# SUBBOARD-MCU.net
KiCad netlist of a schematic drawn in Altium Designer
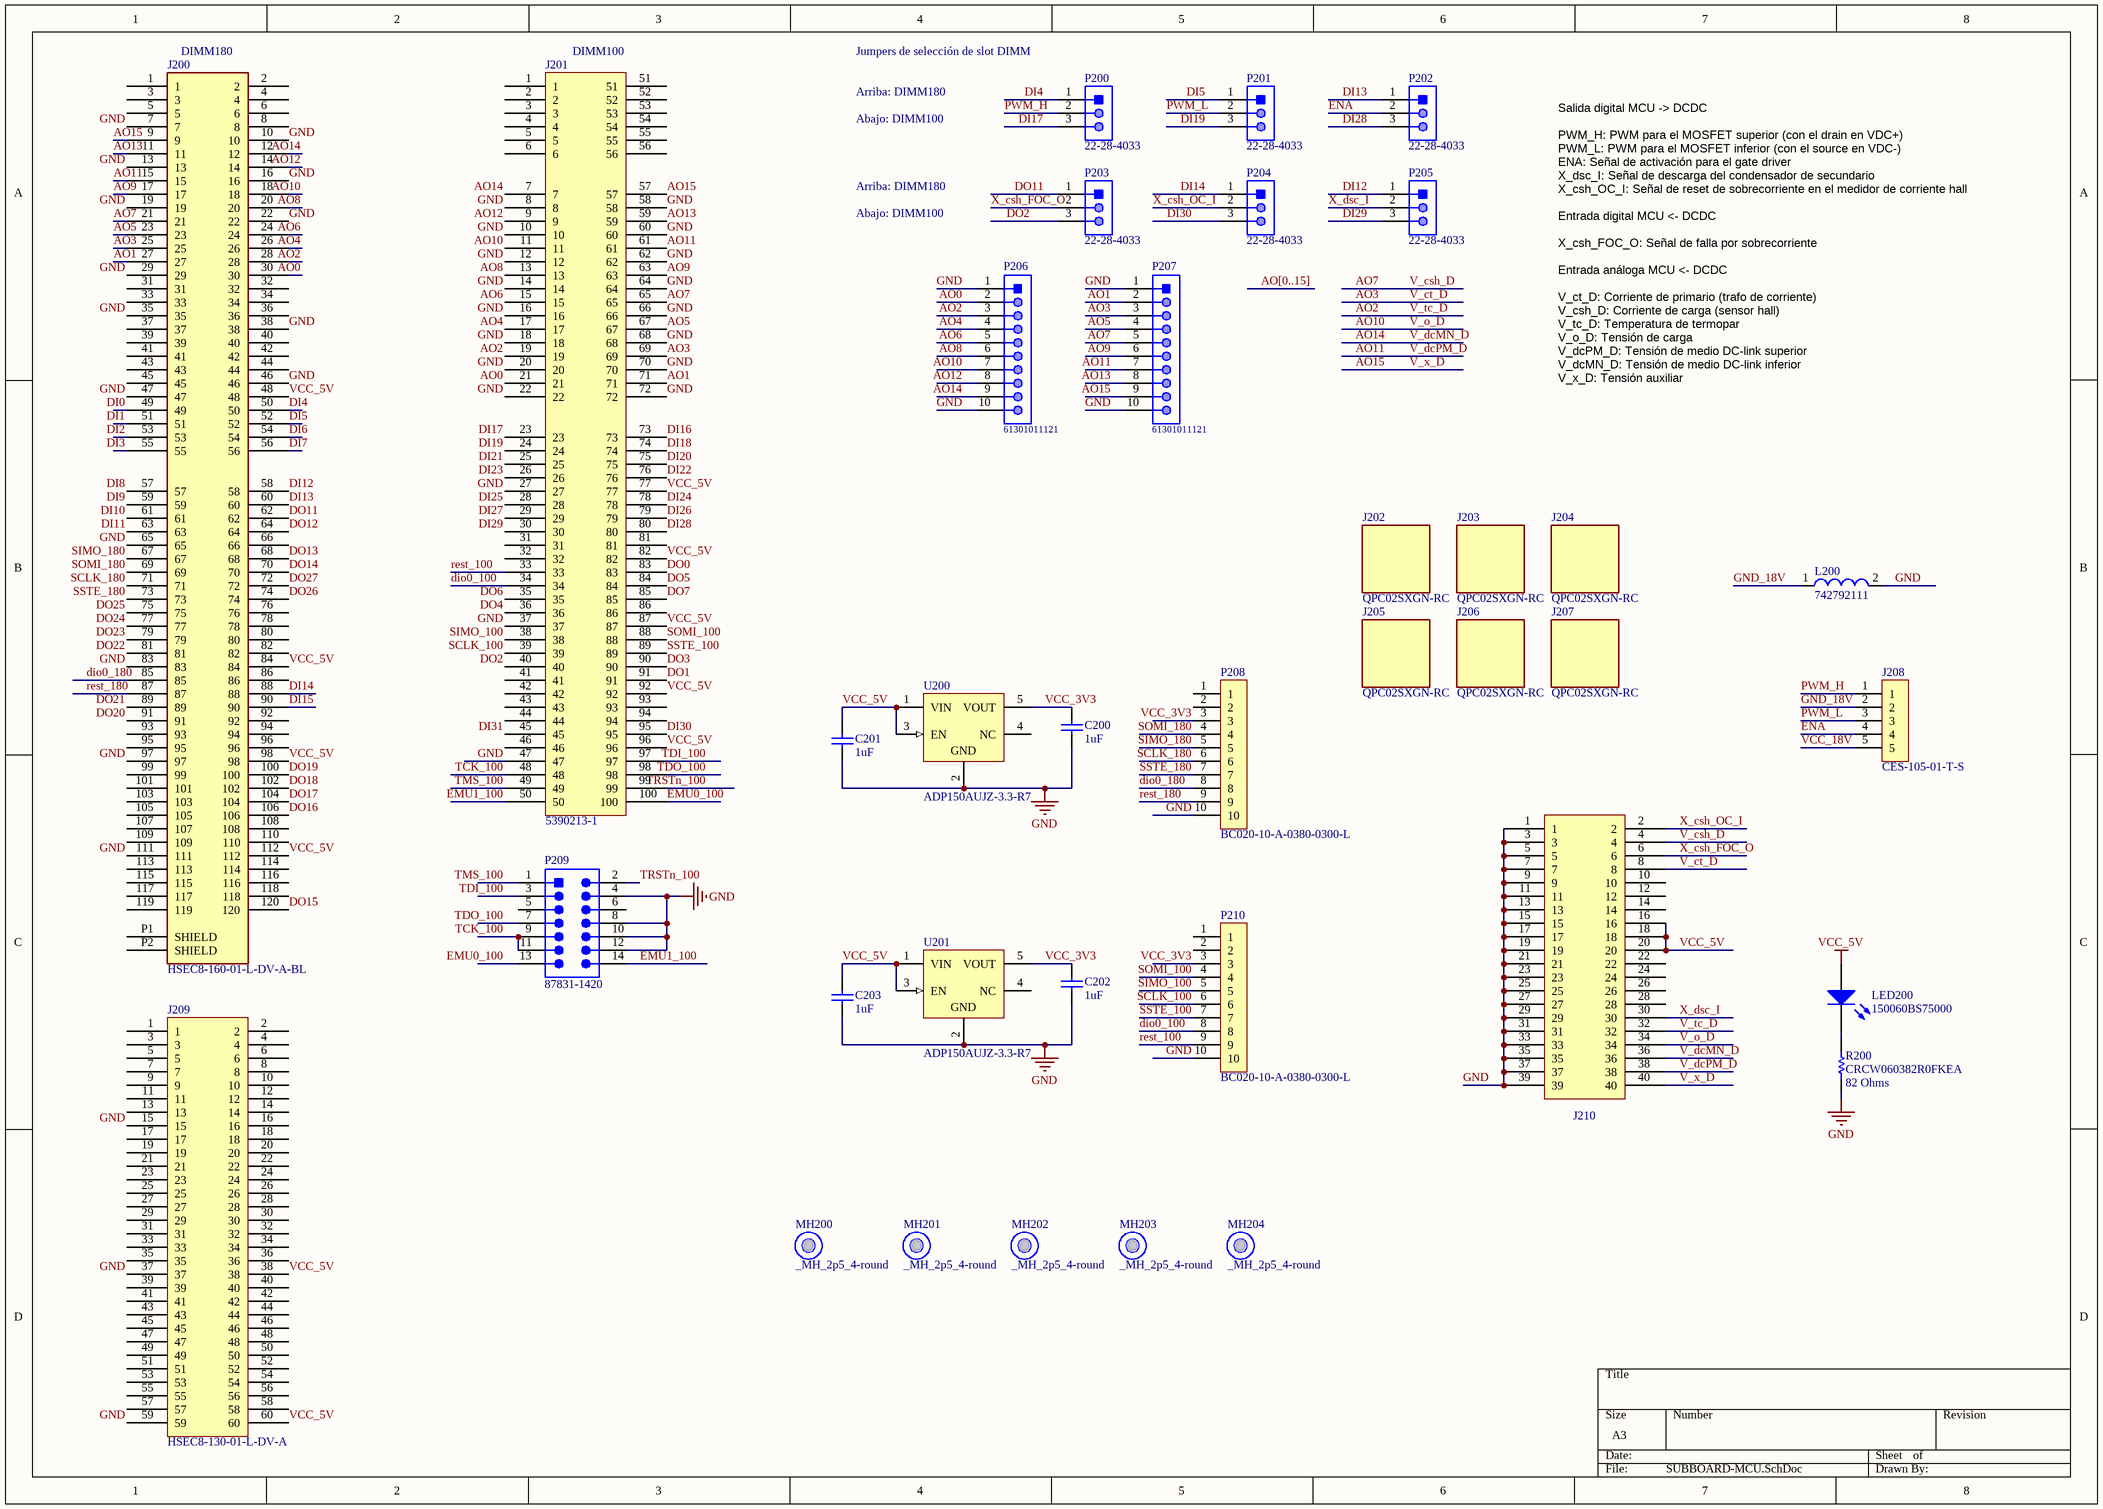
[diagram p0: SUBBOARD-MCU.SchDoc]

(export (version "E")
  (design (tool "Eeschema 10.0.6"))
  (components
    (comp (ref "C200")
      (value "1uF")
      (footprint "CAPC0603(1608)100_N")
      (description "CAP 1uF 50V ±20% 0603 (1608 Metric) Thickness 1mm SMD")
      (fields (field (name "TOLERANCE") "Â±20%") (field (name "Comment") "CAP 1uF 50V 0603(1608)"))
      (libsource (lib "Altium Content Vault") (part "CAP"))
    )
    (comp (ref "C201")
      (value "1uF")
      (footprint "CAPC0603(1608)100_N")
      (description "CAP 1uF 50V ±20% 0603 (1608 Metric) Thickness 1mm SMD")
      (fields (field (name "TOLERANCE") "Â±20%") (field (name "Comment") "CAP 1uF 50V 0603(1608)"))
      (libsource (lib "Altium Content Vault") (part "CAP"))
    )
    (comp (ref "C202")
      (value "1uF")
      (footprint "CAPC0603(1608)100_N")
      (description "CAP 1uF 50V ±20% 0603 (1608 Metric) Thickness 1mm SMD")
      (fields (field (name "TOLERANCE") "Â±20%") (field (name "Comment") "CAP 1uF 50V 0603(1608)"))
      (libsource (lib "Altium Content Vault") (part "CAP"))
    )
    (comp (ref "C203")
      (value "1uF")
      (footprint "CAPC0603(1608)100_N")
      (description "CAP 1uF 50V ±20% 0603 (1608 Metric) Thickness 1mm SMD")
      (fields (field (name "TOLERANCE") "Â±20%") (field (name "Comment") "CAP 1uF 50V 0603(1608)"))
      (libsource (lib "Altium Content Vault") (part "CAP"))
    )
    (comp (ref "J200")
      (value "HSEC8-160-01-L-DV-A-BL")
      (footprint "HSEC8-160-01-L-DV-A-BL")
      (description "Standard Card Edge Connectors 0.80 mm Edge Rate High-Speed Edge Card Connector, Vertical")
      (fields (field (name "MANUFACTURER") "Samtec"))
      (libsource (lib "Altium_Library_POWERLAB") (part "HSEC8-160-01-L-DV-A-BL"))
    )
    (comp (ref "J201")
      (value "5390213-1")
      (footprint "TE_5390213-1")
      (description "100 Position DIMM DRAM Socket Through Hole")
      (fields (field (name "MF") "TE Connectivity"))
      (libsource (lib "Altium_Library_POWERLAB") (part "5390213-1"))
    )
    (comp (ref "J202")
      (value "QPC02SXGN-RC")
      (footprint "FP-QPC02SXGN-RC-MFG")
      (description "CONN JUMPER SHORTING .100\" GOLD")
      (fields
        (field (name "MANUFACTURER") "Sullins")
        (field (name "OCTOPART") "https://octopart.com/qpc02sxgn-rc-sullins-19878795")
      )
      (libsource (lib "Altium Content Vault") (part "87292ac8601c6cf2061292f5bede09e"))
    )
    (comp (ref "J203")
      (value "QPC02SXGN-RC")
      (footprint "FP-QPC02SXGN-RC-MFG")
      (description "CONN JUMPER SHORTING .100\" GOLD")
      (fields
        (field (name "MANUFACTURER") "Sullins")
        (field (name "OCTOPART") "https://octopart.com/qpc02sxgn-rc-sullins-19878795")
      )
      (libsource (lib "Altium Content Vault") (part "87292ac8601c6cf2061292f5bede09e"))
    )
    (comp (ref "J204")
      (value "QPC02SXGN-RC")
      (footprint "FP-QPC02SXGN-RC-MFG")
      (description "CONN JUMPER SHORTING .100\" GOLD")
      (fields
        (field (name "MANUFACTURER") "Sullins")
        (field (name "OCTOPART") "https://octopart.com/qpc02sxgn-rc-sullins-19878795")
      )
      (libsource (lib "Altium Content Vault") (part "87292ac8601c6cf2061292f5bede09e"))
    )
    (comp (ref "J205")
      (value "QPC02SXGN-RC")
      (footprint "FP-QPC02SXGN-RC-MFG")
      (description "CONN JUMPER SHORTING .100\" GOLD")
      (fields
        (field (name "MANUFACTURER") "Sullins")
        (field (name "OCTOPART") "https://octopart.com/qpc02sxgn-rc-sullins-19878795")
      )
      (libsource (lib "Altium Content Vault") (part "87292ac8601c6cf2061292f5bede09e"))
    )
    (comp (ref "J206")
      (value "QPC02SXGN-RC")
      (footprint "FP-QPC02SXGN-RC-MFG")
      (description "CONN JUMPER SHORTING .100\" GOLD")
      (fields
        (field (name "MANUFACTURER") "Sullins")
        (field (name "OCTOPART") "https://octopart.com/qpc02sxgn-rc-sullins-19878795")
      )
      (libsource (lib "Altium Content Vault") (part "87292ac8601c6cf2061292f5bede09e"))
    )
    (comp (ref "J207")
      (value "QPC02SXGN-RC")
      (footprint "FP-QPC02SXGN-RC-MFG")
      (description "CONN JUMPER SHORTING .100\" GOLD")
      (fields
        (field (name "MANUFACTURER") "Sullins")
        (field (name "OCTOPART") "https://octopart.com/qpc02sxgn-rc-sullins-19878795")
      )
      (libsource (lib "Altium Content Vault") (part "87292ac8601c6cf2061292f5bede09e"))
    )
    (comp (ref "J208")
      (value "CES-105-01-T-S")
      (footprint "CES-105-01-T-S")
      (fields (field (name "MANUFACTURER") "Samtec"))
      (libsource (lib "Altium_Library_POWERLAB") (part "CES-105-01-T-S"))
    )
    (comp (ref "J209")
      (value "HSEC8-130-01-L-DV-A")
      (footprint "HSEC8-130-01-L-DV-A")
      (description "Standard Card Edge Connectors 0.80 mm Edge Rate High-Speed Edge Card Connector, Vertical")
      (fields (field (name "MANUFACTURER") "Samtec"))
      (libsource (lib "Altium_Library_POWERLAB") (part "HSEC8-130-01-L-DV-A"))
    )
    (comp (ref "J210")
      (value "CLP-120-02-F-DH")
      (footprint "CLP-120-02-F-DH")
      (fields (field (name "MANUFACTURER") "Samtec"))
      (libsource (lib "Altium_Library_POWERLAB") (part "CLP-120-02-F-DH"))
    )
    (comp (ref "L200")
      (value "742792111")
      (footprint "SMD-1206")
      (description "SMD EMI Suppression Ferrite Bead WE-CBF, Z = 26 Ohm")
      (libsource (lib "Altium Content Vault") (part "PAS-IND-INDUCTOR-2"))
    )
    (comp (ref "LED200")
      (value "150060BS75000")
      (footprint "0603_A")
      (description "SMD mono-color Chip LED, WL-SMCW, Blue")
      (fields (field (name "MANUFACTURER") "Wuerth Elektronik"))
      (libsource (lib "Altium Content Vault") (part "WE-LED_K1A2-2"))
    )
    (comp (ref "MH200")
      (value "_MH_2p5_4-round")
      (footprint "_MH_2p5_4-round")
      (description "matching hole 2.5 hole, 4mm pad (round)")
      (libsource (lib "Altium_Library_POWERLAB") (part "_MH_2p5_4-round"))
    )
    (comp (ref "MH201")
      (value "_MH_2p5_4-round")
      (footprint "_MH_2p5_4-round")
      (description "matching hole 2.5 hole, 4mm pad (round)")
      (libsource (lib "Altium_Library_POWERLAB") (part "_MH_2p5_4-round"))
    )
    (comp (ref "MH202")
      (value "_MH_2p5_4-round")
      (footprint "_MH_2p5_4-round")
      (description "matching hole 2.5 hole, 4mm pad (round)")
      (libsource (lib "Altium_Library_POWERLAB") (part "_MH_2p5_4-round"))
    )
    (comp (ref "MH203")
      (value "_MH_2p5_4-round")
      (footprint "_MH_2p5_4-round")
      (description "matching hole 2.5 hole, 4mm pad (round)")
      (libsource (lib "Altium_Library_POWERLAB") (part "_MH_2p5_4-round"))
    )
    (comp (ref "MH204")
      (value "_MH_2p5_4-round")
      (footprint "_MH_2p5_4-round")
      (description "matching hole 2.5 hole, 4mm pad (round)")
      (libsource (lib "Altium_Library_POWERLAB") (part "_MH_2p5_4-round"))
    )
    (comp (ref "P200")
      (value "22-28-4033")
      (footprint "MOLX-22-28-4033_V")
      (description "Male Header, Pitch 2.54 mm, 1 x 3 Position, Height 8.38 mm, Tail Length 3.18 mm, RoHS, Bulk")
      (fields (field (name "MANUFACTURER") "Molex"))
      (libsource (lib "Altium Content Vault") (part "CN-1P-M-R3"))
    )
    (comp (ref "P201")
      (value "22-28-4033")
      (footprint "MOLX-22-28-4033_V")
      (description "Male Header, Pitch 2.54 mm, 1 x 3 Position, Height 8.38 mm, Tail Length 3.18 mm, RoHS, Bulk")
      (fields (field (name "MANUFACTURER") "Molex"))
      (libsource (lib "Altium Content Vault") (part "CN-1P-M-R3"))
    )
    (comp (ref "P202")
      (value "22-28-4033")
      (footprint "MOLX-22-28-4033_V")
      (description "Male Header, Pitch 2.54 mm, 1 x 3 Position, Height 8.38 mm, Tail Length 3.18 mm, RoHS, Bulk")
      (fields (field (name "MANUFACTURER") "Molex"))
      (libsource (lib "Altium Content Vault") (part "CN-1P-M-R3"))
    )
    (comp (ref "P203")
      (value "22-28-4033")
      (footprint "MOLX-22-28-4033_V")
      (description "Male Header, Pitch 2.54 mm, 1 x 3 Position, Height 8.38 mm, Tail Length 3.18 mm, RoHS, Bulk")
      (fields (field (name "MANUFACTURER") "Molex"))
      (libsource (lib "Altium Content Vault") (part "CN-1P-M-R3"))
    )
    (comp (ref "P204")
      (value "22-28-4033")
      (footprint "MOLX-22-28-4033_V")
      (description "Male Header, Pitch 2.54 mm, 1 x 3 Position, Height 8.38 mm, Tail Length 3.18 mm, RoHS, Bulk")
      (fields (field (name "MANUFACTURER") "Molex"))
      (libsource (lib "Altium Content Vault") (part "CN-1P-M-R3"))
    )
    (comp (ref "P205")
      (value "22-28-4033")
      (footprint "MOLX-22-28-4033_V")
      (description "Male Header, Pitch 2.54 mm, 1 x 3 Position, Height 8.38 mm, Tail Length 3.18 mm, RoHS, Bulk")
      (fields (field (name "MANUFACTURER") "Molex"))
      (libsource (lib "Altium Content Vault") (part "CN-1P-M-R3"))
    )
    (comp (ref "P206")
      (value "61301011121")
      (footprint "61301011121")
      (description "THT Vertical Pin Header WR-PHD, Pitch 2.54 mm, Single Row, 10 pins")
      (fields (field (name "MANUFACTURER") "Wurth Elektronik") (field (name "PUBLISHER") "WurthElektronik"))
      (libsource (lib "Altium Content Vault") (part "WE-CN-1P-M-R10"))
    )
    (comp (ref "P207")
      (value "61301011121")
      (footprint "61301011121")
      (description "THT Vertical Pin Header WR-PHD, Pitch 2.54 mm, Single Row, 10 pins")
      (fields (field (name "MANUFACTURER") "Wurth Elektronik") (field (name "PUBLISHER") "WurthElektronik"))
      (libsource (lib "Altium Content Vault") (part "WE-CN-1P-M-R10"))
    )
    (comp (ref "P208")
      (value "BC020-10-A-0380-0300-L")
      (footprint "BC020-10-A-0380-0300-L")
      (fields (field (name "MANUFACTURER") "Global Connector Technology"))
      (libsource (lib "Altium_Library_POWERLAB") (part "BC020-10-A-0380-0300-L"))
    )
    (comp (ref "P209")
      (value "87831-1420")
      (footprint "MOLEX-87831-1420_V")
      (description "Header, Pitch 2 mm, 2 x 7 Position, Height 6.4 mm, Tail Length 2.5 mm, -55 to 105 degC, RoHS, Tube")
      (fields (field (name "MANUFACTURER") "Molex"))
      (libsource (lib "Altium Content Vault") (part "CN-2P-M-R14"))
    )
    (comp (ref "P210")
      (value "BC020-10-A-0380-0300-L")
      (footprint "BC020-10-A-0380-0300-L")
      (fields (field (name "MANUFACTURER") "Global Connector Technology"))
      (libsource (lib "Altium_Library_POWERLAB") (part "BC020-10-A-0380-0300-L"))
    )
    (comp (ref "R200")
      (value "CRCW060382R0FKEA")
      (footprint "RESC1609X50X30LL10T20")
      (fields (field (name "MANUFACTURER") "Vishay Dale") (field (name "ALTIUM_VALUE") "82 Ohms"))
      (libsource (lib "Altium Content Vault") (part "RES"))
    )
    (comp (ref "U200")
      (value "ADP150AUJZ-3.3-R7")
      (footprint "ADI-UJ-5_M")
      (fields (field (name "MANUFACTURER") "Analog Devices"))
      (libsource (lib "Altium Content Vault") (part "ADI-ADP1XX-UJ-5"))
    )
    (comp (ref "U201")
      (value "ADP150AUJZ-3.3-R7")
      (footprint "ADI-UJ-5_M")
      (fields (field (name "MANUFACTURER") "Analog Devices"))
      (libsource (lib "Altium Content Vault") (part "ADI-ADP1XX-UJ-5"))
    )
  )
  (nets
    (net (code "1") (name "/AO0") (class "Default")
      (node (ref "J200") (pin "30") (pinfunction "30_30") (pintype "passive"))
      (node (ref "J201") (pin "21") (pinfunction "21_21") (pintype "power_in"))
      (node (ref "P206") (pin "2") (pinfunction "2_2") (pintype "passive"))
    )
    (net (code "2") (name "/AO1") (class "Default")
      (node (ref "J200") (pin "27") (pinfunction "27_27") (pintype "passive"))
      (node (ref "J201") (pin "71") (pinfunction "71_71") (pintype "power_in"))
      (node (ref "P207") (pin "2") (pinfunction "2_2") (pintype "passive"))
    )
    (net (code "3") (name "/AO2") (class "Default")
      (node (ref "J200") (pin "28") (pinfunction "28_28") (pintype "passive"))
      (node (ref "J201") (pin "19") (pinfunction "19_19") (pintype "power_in"))
      (node (ref "J210") (pin "32") (pinfunction "32_32") (pintype "passive"))
      (node (ref "P206") (pin "3") (pinfunction "3_3") (pintype "passive"))
    )
    (net (code "4") (name "/AO3") (class "Default")
      (node (ref "J200") (pin "25") (pinfunction "25_25") (pintype "passive"))
      (node (ref "J201") (pin "69") (pinfunction "69_69") (pintype "power_in"))
      (node (ref "J210") (pin "8") (pinfunction "8_8") (pintype "passive"))
      (node (ref "P207") (pin "3") (pinfunction "3_3") (pintype "passive"))
    )
    (net (code "5") (name "/AO4") (class "Default")
      (node (ref "J200") (pin "26") (pinfunction "26_26") (pintype "passive"))
      (node (ref "J201") (pin "17") (pinfunction "17_17") (pintype "power_in"))
      (node (ref "P206") (pin "4") (pinfunction "4_4") (pintype "passive"))
    )
    (net (code "6") (name "/AO5") (class "Default")
      (node (ref "J200") (pin "23") (pinfunction "23_23") (pintype "passive"))
      (node (ref "J201") (pin "67") (pinfunction "67_67") (pintype "power_in"))
      (node (ref "P207") (pin "4") (pinfunction "4_4") (pintype "passive"))
    )
    (net (code "7") (name "/AO6") (class "Default")
      (node (ref "J200") (pin "24") (pinfunction "24_24") (pintype "passive"))
      (node (ref "J201") (pin "15") (pinfunction "15_15") (pintype "power_in"))
      (node (ref "P206") (pin "5") (pinfunction "5_5") (pintype "passive"))
    )
    (net (code "8") (name "/AO7") (class "Default")
      (node (ref "J200") (pin "21") (pinfunction "21_21") (pintype "passive"))
      (node (ref "J201") (pin "65") (pinfunction "65_65") (pintype "power_in"))
      (node (ref "J210") (pin "4") (pinfunction "4_4") (pintype "passive"))
      (node (ref "P207") (pin "5") (pinfunction "5_5") (pintype "passive"))
    )
    (net (code "9") (name "/AO8") (class "Default")
      (node (ref "J200") (pin "20") (pinfunction "20_20") (pintype "passive"))
      (node (ref "J201") (pin "13") (pinfunction "13_13") (pintype "power_in"))
      (node (ref "P206") (pin "6") (pinfunction "6_6") (pintype "passive"))
    )
    (net (code "10") (name "/AO9") (class "Default")
      (node (ref "J200") (pin "17") (pinfunction "17_17") (pintype "passive"))
      (node (ref "J201") (pin "63") (pinfunction "63_63") (pintype "power_in"))
      (node (ref "P207") (pin "6") (pinfunction "6_6") (pintype "passive"))
    )
    (net (code "11") (name "/AO10") (class "Default")
      (node (ref "J200") (pin "18") (pinfunction "18_18") (pintype "passive"))
      (node (ref "J201") (pin "11") (pinfunction "11_11") (pintype "power_in"))
      (node (ref "J210") (pin "34") (pinfunction "34_34") (pintype "passive"))
      (node (ref "P206") (pin "7") (pinfunction "7_7") (pintype "passive"))
    )
    (net (code "12") (name "/AO11") (class "Default")
      (node (ref "J200") (pin "15") (pinfunction "15_15") (pintype "passive"))
      (node (ref "J201") (pin "61") (pinfunction "61_61") (pintype "power_in"))
      (node (ref "J210") (pin "38") (pinfunction "38_38") (pintype "passive"))
      (node (ref "P207") (pin "7") (pinfunction "7_7") (pintype "passive"))
    )
    (net (code "13") (name "/AO12") (class "Default")
      (node (ref "J200") (pin "14") (pinfunction "14_14") (pintype "passive"))
      (node (ref "J201") (pin "9") (pinfunction "9_9") (pintype "power_in"))
      (node (ref "P206") (pin "8") (pinfunction "8_8") (pintype "passive"))
    )
    (net (code "14") (name "/AO13") (class "Default")
      (node (ref "J200") (pin "11") (pinfunction "11_11") (pintype "passive"))
      (node (ref "J201") (pin "59") (pinfunction "59_59") (pintype "power_in"))
      (node (ref "P207") (pin "8") (pinfunction "8_8") (pintype "passive"))
    )
    (net (code "15") (name "/AO14") (class "Default")
      (node (ref "J200") (pin "12") (pinfunction "12_12") (pintype "passive"))
      (node (ref "J201") (pin "7") (pinfunction "7_7") (pintype "power_in"))
      (node (ref "J210") (pin "36") (pinfunction "36_36") (pintype "passive"))
      (node (ref "P206") (pin "9") (pinfunction "9_9") (pintype "passive"))
    )
    (net (code "16") (name "/AO15") (class "Default")
      (node (ref "J200") (pin "9") (pinfunction "9_9") (pintype "passive"))
      (node (ref "J201") (pin "57") (pinfunction "57_57") (pintype "power_in"))
      (node (ref "J210") (pin "40") (pinfunction "40_40") (pintype "passive"))
      (node (ref "P207") (pin "9") (pinfunction "9_9") (pintype "passive"))
    )
    (net (code "18") (name "/DI0") (class "Default")
      (node (ref "J200") (pin "49") (pinfunction "49_49") (pintype "passive"))
    )
    (net (code "19") (name "/DI1") (class "Default")
      (node (ref "J200") (pin "51") (pinfunction "51_51") (pintype "passive"))
    )
    (net (code "20") (name "/DI2") (class "Default")
      (node (ref "J200") (pin "53") (pinfunction "53_53") (pintype "passive"))
    )
    (net (code "21") (name "/DI3") (class "Default")
      (node (ref "J200") (pin "55") (pinfunction "55_55") (pintype "passive"))
    )
    (net (code "22") (name "/DI4") (class "Default")
      (node (ref "J200") (pin "50") (pinfunction "50_50") (pintype "passive"))
      (node (ref "P200") (pin "1") (pinfunction "1_1") (pintype "passive"))
    )
    (net (code "23") (name "/DI5") (class "Default")
      (node (ref "J200") (pin "52") (pinfunction "52_52") (pintype "passive"))
      (node (ref "P201") (pin "1") (pinfunction "1_1") (pintype "passive"))
    )
    (net (code "24") (name "/DI6") (class "Default")
      (node (ref "J200") (pin "54") (pinfunction "54_54") (pintype "passive"))
    )
    (net (code "25") (name "/DI7") (class "Default")
      (node (ref "J200") (pin "56") (pinfunction "56_56") (pintype "passive"))
    )
    (net (code "26") (name "/DI8") (class "Default")
      (node (ref "J200") (pin "57") (pinfunction "57_57") (pintype "passive"))
    )
    (net (code "27") (name "/DI9") (class "Default")
      (node (ref "J200") (pin "59") (pinfunction "59_59") (pintype "passive"))
    )
    (net (code "28") (name "/DI10") (class "Default")
      (node (ref "J200") (pin "61") (pinfunction "61_61") (pintype "passive"))
    )
    (net (code "29") (name "/DI11") (class "Default")
      (node (ref "J200") (pin "63") (pinfunction "63_63") (pintype "passive"))
    )
    (net (code "30") (name "/DI12") (class "Default")
      (node (ref "J200") (pin "58") (pinfunction "58_58") (pintype "passive"))
      (node (ref "P205") (pin "1") (pinfunction "1_1") (pintype "passive"))
    )
    (net (code "31") (name "/DI13") (class "Default")
      (node (ref "J200") (pin "60") (pinfunction "60_60") (pintype "passive"))
      (node (ref "P202") (pin "1") (pinfunction "1_1") (pintype "passive"))
    )
    (net (code "32") (name "/DI14") (class "Default")
      (node (ref "J200") (pin "88") (pinfunction "88_88") (pintype "passive"))
      (node (ref "P204") (pin "1") (pinfunction "1_1") (pintype "passive"))
    )
    (net (code "33") (name "/DI15") (class "Default")
      (node (ref "J200") (pin "90") (pinfunction "90_90") (pintype "passive"))
    )
    (net (code "34") (name "/DI16") (class "Default")
      (node (ref "J201") (pin "73") (pinfunction "73_73") (pintype "power_in"))
    )
    (net (code "35") (name "/DI17") (class "Default")
      (node (ref "J201") (pin "23") (pinfunction "23_23") (pintype "power_in"))
      (node (ref "P200") (pin "3") (pinfunction "3_3") (pintype "passive"))
    )
    (net (code "36") (name "/DI18") (class "Default")
      (node (ref "J201") (pin "74") (pinfunction "74_74") (pintype "power_in"))
    )
    (net (code "37") (name "/DI19") (class "Default")
      (node (ref "J201") (pin "24") (pinfunction "24_24") (pintype "power_in"))
      (node (ref "P201") (pin "3") (pinfunction "3_3") (pintype "passive"))
    )
    (net (code "38") (name "/DI20") (class "Default")
      (node (ref "J201") (pin "75") (pinfunction "75_75") (pintype "power_in"))
    )
    (net (code "39") (name "/DI21") (class "Default")
      (node (ref "J201") (pin "25") (pinfunction "25_25") (pintype "power_in"))
    )
    (net (code "40") (name "/DI22") (class "Default")
      (node (ref "J201") (pin "76") (pinfunction "76_76") (pintype "power_in"))
    )
    (net (code "41") (name "/DI23") (class "Default")
      (node (ref "J201") (pin "26") (pinfunction "26_26") (pintype "power_in"))
    )
    (net (code "42") (name "/DI24") (class "Default")
      (node (ref "J201") (pin "78") (pinfunction "78_78") (pintype "power_in"))
    )
    (net (code "43") (name "/DI25") (class "Default")
      (node (ref "J201") (pin "28") (pinfunction "28_28") (pintype "power_in"))
    )
    (net (code "44") (name "/DI26") (class "Default")
      (node (ref "J201") (pin "79") (pinfunction "79_79") (pintype "power_in"))
    )
    (net (code "45") (name "/DI27") (class "Default")
      (node (ref "J201") (pin "29") (pinfunction "29_29") (pintype "power_in"))
    )
    (net (code "46") (name "/DI28") (class "Default")
      (node (ref "J201") (pin "80") (pinfunction "80_80") (pintype "power_in"))
      (node (ref "P202") (pin "3") (pinfunction "3_3") (pintype "passive"))
    )
    (net (code "47") (name "/DI29") (class "Default")
      (node (ref "J201") (pin "30") (pinfunction "30_30") (pintype "power_in"))
      (node (ref "P205") (pin "3") (pinfunction "3_3") (pintype "passive"))
    )
    (net (code "48") (name "/DI30") (class "Default")
      (node (ref "J201") (pin "95") (pinfunction "95_95") (pintype "power_in"))
      (node (ref "P204") (pin "3") (pinfunction "3_3") (pintype "passive"))
    )
    (net (code "49") (name "/DI31") (class "Default")
      (node (ref "J201") (pin "45") (pinfunction "45_45") (pintype "power_in"))
    )
    (net (code "50") (name "/DO0") (class "Default")
      (node (ref "J201") (pin "83") (pinfunction "83_83") (pintype "power_in"))
    )
    (net (code "51") (name "/DO1") (class "Default")
      (node (ref "J201") (pin "91") (pinfunction "91_91") (pintype "power_in"))
    )
    (net (code "52") (name "/DO2") (class "Default")
      (node (ref "J201") (pin "40") (pinfunction "40_40") (pintype "power_in"))
      (node (ref "P203") (pin "3") (pinfunction "3_3") (pintype "passive"))
    )
    (net (code "53") (name "/DO3") (class "Default")
      (node (ref "J201") (pin "90") (pinfunction "90_90") (pintype "power_in"))
    )
    (net (code "54") (name "/DO4") (class "Default")
      (node (ref "J201") (pin "36") (pinfunction "36_36") (pintype "power_in"))
    )
    (net (code "55") (name "/DO5") (class "Default")
      (node (ref "J201") (pin "84") (pinfunction "84_84") (pintype "power_in"))
    )
    (net (code "56") (name "/DO6") (class "Default")
      (node (ref "J201") (pin "35") (pinfunction "35_35") (pintype "power_in"))
    )
    (net (code "57") (name "/DO7") (class "Default")
      (node (ref "J201") (pin "85") (pinfunction "85_85") (pintype "power_in"))
    )
    (net (code "58") (name "/DO11") (class "Default")
      (node (ref "J200") (pin "62") (pinfunction "62_62") (pintype "passive"))
      (node (ref "P203") (pin "1") (pinfunction "1_1") (pintype "passive"))
    )
    (net (code "59") (name "/DO12") (class "Default")
      (node (ref "J200") (pin "64") (pinfunction "64_64") (pintype "passive"))
    )
    (net (code "60") (name "/DO13") (class "Default")
      (node (ref "J200") (pin "68") (pinfunction "68_68") (pintype "passive"))
    )
    (net (code "61") (name "/DO14") (class "Default")
      (node (ref "J200") (pin "70") (pinfunction "70_70") (pintype "passive"))
    )
    (net (code "62") (name "/DO15") (class "Default")
      (node (ref "J200") (pin "120") (pinfunction "120_120") (pintype "passive"))
    )
    (net (code "63") (name "/DO16") (class "Default")
      (node (ref "J200") (pin "106") (pinfunction "106_106") (pintype "passive"))
    )
    (net (code "64") (name "/DO17") (class "Default")
      (node (ref "J200") (pin "104") (pinfunction "104_104") (pintype "passive"))
    )
    (net (code "65") (name "/DO18") (class "Default")
      (node (ref "J200") (pin "102") (pinfunction "102_102") (pintype "passive"))
    )
    (net (code "66") (name "/DO19") (class "Default")
      (node (ref "J200") (pin "100") (pinfunction "100_100") (pintype "passive"))
    )
    (net (code "67") (name "/DO20") (class "Default")
      (node (ref "J200") (pin "91") (pinfunction "91_91") (pintype "passive"))
    )
    (net (code "68") (name "/DO21") (class "Default")
      (node (ref "J200") (pin "89") (pinfunction "89_89") (pintype "passive"))
    )
    (net (code "69") (name "/DO22") (class "Default")
      (node (ref "J200") (pin "81") (pinfunction "81_81") (pintype "passive"))
    )
    (net (code "70") (name "/DO23") (class "Default")
      (node (ref "J200") (pin "79") (pinfunction "79_79") (pintype "passive"))
    )
    (net (code "71") (name "/DO24") (class "Default")
      (node (ref "J200") (pin "77") (pinfunction "77_77") (pintype "passive"))
    )
    (net (code "72") (name "/DO25") (class "Default")
      (node (ref "J200") (pin "75") (pinfunction "75_75") (pintype "passive"))
    )
    (net (code "73") (name "/DO26") (class "Default")
      (node (ref "J200") (pin "74") (pinfunction "74_74") (pintype "passive"))
    )
    (net (code "74") (name "/DO27") (class "Default")
      (node (ref "J200") (pin "72") (pinfunction "72_72") (pintype "passive"))
    )
    (net (code "75") (name "/EMU0_100") (class "Default")
      (node (ref "J201") (pin "100") (pinfunction "100_100") (pintype "power_in"))
      (node (ref "P209") (pin "13") (pinfunction "13_13") (pintype "passive"))
    )
    (net (code "76") (name "/EMU1_100") (class "Default")
      (node (ref "J201") (pin "50") (pinfunction "50_50") (pintype "power_in"))
      (node (ref "P209") (pin "14") (pinfunction "14_14") (pintype "passive"))
    )
    (net (code "77") (name "/ENA") (class "Default")
      (node (ref "J208") (pin "4") (pinfunction "4_4") (pintype "passive"))
      (node (ref "P202") (pin "2") (pinfunction "2_2") (pintype "passive"))
    )
    (net (code "78") (name "/GND_18V") (class "Default")
      (node (ref "J208") (pin "2") (pinfunction "2_2") (pintype "passive"))
      (node (ref "L200") (pin "1") (pinfunction "1_1") (pintype "passive"))
    )
    (net (code "79") (name "/PWM_H") (class "Default")
      (node (ref "J208") (pin "1") (pinfunction "1_1") (pintype "passive"))
      (node (ref "P200") (pin "2") (pinfunction "2_2") (pintype "passive"))
    )
    (net (code "80") (name "/PWM_L") (class "Default")
      (node (ref "J208") (pin "3") (pinfunction "3_3") (pintype "passive"))
      (node (ref "P201") (pin "2") (pinfunction "2_2") (pintype "passive"))
    )
    (net (code "81") (name "/SCLK_100") (class "Default")
      (node (ref "J201") (pin "39") (pinfunction "39_39") (pintype "power_in"))
      (node (ref "P210") (pin "6") (pinfunction "6_6") (pintype "passive"))
    )
    (net (code "82") (name "/SCLK_180") (class "Default")
      (node (ref "J200") (pin "71") (pinfunction "71_71") (pintype "passive"))
      (node (ref "P208") (pin "6") (pinfunction "6_6") (pintype "passive"))
    )
    (net (code "83") (name "/SIMO_100") (class "Default")
      (node (ref "J201") (pin "38") (pinfunction "38_38") (pintype "power_in"))
      (node (ref "P210") (pin "5") (pinfunction "5_5") (pintype "passive"))
    )
    (net (code "84") (name "/SIMO_180") (class "Default")
      (node (ref "J200") (pin "67") (pinfunction "67_67") (pintype "passive"))
      (node (ref "P208") (pin "5") (pinfunction "5_5") (pintype "passive"))
    )
    (net (code "85") (name "/SOMI_100") (class "Default")
      (node (ref "J201") (pin "88") (pinfunction "88_88") (pintype "power_in"))
      (node (ref "P210") (pin "4") (pinfunction "4_4") (pintype "passive"))
    )
    (net (code "86") (name "/SOMI_180") (class "Default")
      (node (ref "J200") (pin "69") (pinfunction "69_69") (pintype "passive"))
      (node (ref "P208") (pin "4") (pinfunction "4_4") (pintype "passive"))
    )
    (net (code "87") (name "/SSTE_100") (class "Default")
      (node (ref "J201") (pin "89") (pinfunction "89_89") (pintype "power_in"))
      (node (ref "P210") (pin "7") (pinfunction "7_7") (pintype "passive"))
    )
    (net (code "88") (name "/SSTE_180") (class "Default")
      (node (ref "J200") (pin "73") (pinfunction "73_73") (pintype "passive"))
      (node (ref "P208") (pin "7") (pinfunction "7_7") (pintype "passive"))
    )
    (net (code "89") (name "/TCK_100") (class "Default")
      (node (ref "J201") (pin "48") (pinfunction "48_48") (pintype "power_in"))
      (node (ref "P209") (pin "11") (pinfunction "11_11") (pintype "passive"))
      (node (ref "P209") (pin "9") (pinfunction "9_9") (pintype "passive"))
    )
    (net (code "90") (name "/TDI_100") (class "Default")
      (node (ref "J201") (pin "97") (pinfunction "97_97") (pintype "power_in"))
      (node (ref "P209") (pin "3") (pinfunction "3_3") (pintype "passive"))
    )
    (net (code "91") (name "/TDO_100") (class "Default")
      (node (ref "J201") (pin "98") (pinfunction "98_98") (pintype "power_in"))
      (node (ref "P209") (pin "7") (pinfunction "7_7") (pintype "passive"))
    )
    (net (code "92") (name "/TMS_100") (class "Default")
      (node (ref "J201") (pin "49") (pinfunction "49_49") (pintype "power_in"))
      (node (ref "P209") (pin "1") (pinfunction "1_1") (pintype "passive"))
    )
    (net (code "93") (name "/TRSTn_100") (class "Default")
      (node (ref "J201") (pin "99") (pinfunction "99_99") (pintype "power_in"))
      (node (ref "P209") (pin "2") (pinfunction "2_2") (pintype "passive"))
    )
    (net (code "94") (name "/VCC_3V3") (class "Default")
      (node (ref "C200") (pin "2") (pinfunction "2_2") (pintype "passive"))
      (node (ref "C202") (pin "2") (pinfunction "2_2") (pintype "passive"))
      (node (ref "P208") (pin "3") (pinfunction "3_3") (pintype "passive"))
      (node (ref "P210") (pin "3") (pinfunction "3_3") (pintype "passive"))
      (node (ref "U200") (pin "5") (pinfunction "VOUT_5") (pintype "power_in"))
      (node (ref "U201") (pin "5") (pinfunction "VOUT_5") (pintype "power_in"))
    )
    (net (code "95") (name "/VCC_18V") (class "Default")
      (node (ref "J208") (pin "5") (pinfunction "5_5") (pintype "passive"))
    )
    (net (code "96") (name "/X_csh_FOC_O") (class "Default")
      (node (ref "J210") (pin "6") (pinfunction "6_6") (pintype "passive"))
      (node (ref "P203") (pin "2") (pinfunction "2_2") (pintype "passive"))
    )
    (net (code "97") (name "/X_csh_OC_I") (class "Default")
      (node (ref "J210") (pin "2") (pinfunction "2_2") (pintype "passive"))
      (node (ref "P204") (pin "2") (pinfunction "2_2") (pintype "passive"))
    )
    (net (code "98") (name "/X_dsc_I") (class "Default")
      (node (ref "J210") (pin "30") (pinfunction "30_30") (pintype "passive"))
      (node (ref "P205") (pin "2") (pinfunction "2_2") (pintype "passive"))
    )
    (net (code "99") (name "/dio0_100") (class "Default")
      (node (ref "J201") (pin "34") (pinfunction "34_34") (pintype "power_in"))
      (node (ref "P210") (pin "8") (pinfunction "8_8") (pintype "passive"))
    )
    (net (code "100") (name "/dio0_180") (class "Default")
      (node (ref "J200") (pin "85") (pinfunction "85_85") (pintype "passive"))
      (node (ref "P208") (pin "8") (pinfunction "8_8") (pintype "passive"))
    )
    (net (code "101") (name "/rest_100") (class "Default")
      (node (ref "J201") (pin "33") (pinfunction "33_33") (pintype "power_in"))
      (node (ref "P210") (pin "9") (pinfunction "9_9") (pintype "passive"))
    )
    (net (code "102") (name "/rest_180") (class "Default")
      (node (ref "J200") (pin "87") (pinfunction "87_87") (pintype "passive"))
      (node (ref "P208") (pin "9") (pinfunction "9_9") (pintype "passive"))
    )
    (net (code "103") (name "GND") (class "Default")
      (node (ref "C200") (pin "1") (pinfunction "1_1") (pintype "passive"))
      (node (ref "C201") (pin "1") (pinfunction "1_1") (pintype "passive"))
      (node (ref "C202") (pin "1") (pinfunction "1_1") (pintype "passive"))
      (node (ref "C203") (pin "1") (pinfunction "1_1") (pintype "passive"))
      (node (ref "J200") (pin "10") (pinfunction "10_10") (pintype "passive"))
      (node (ref "J200") (pin "111") (pinfunction "111_111") (pintype "passive"))
      (node (ref "J200") (pin "13") (pinfunction "13_13") (pintype "passive"))
      (node (ref "J200") (pin "16") (pinfunction "16_16") (pintype "passive"))
      (node (ref "J200") (pin "19") (pinfunction "19_19") (pintype "passive"))
      (node (ref "J200") (pin "22") (pinfunction "22_22") (pintype "passive"))
      (node (ref "J200") (pin "29") (pinfunction "29_29") (pintype "passive"))
      (node (ref "J200") (pin "35") (pinfunction "35_35") (pintype "passive"))
      (node (ref "J200") (pin "38") (pinfunction "38_38") (pintype "passive"))
      (node (ref "J200") (pin "46") (pinfunction "46_46") (pintype "passive"))
      (node (ref "J200") (pin "47") (pinfunction "47_47") (pintype "passive"))
      (node (ref "J200") (pin "65") (pinfunction "65_65") (pintype "passive"))
      (node (ref "J200") (pin "7") (pinfunction "7_7") (pintype "passive"))
      (node (ref "J200") (pin "83") (pinfunction "83_83") (pintype "passive"))
      (node (ref "J200") (pin "97") (pinfunction "97_97") (pintype "passive"))
      (node (ref "J201") (pin "10") (pinfunction "10_10") (pintype "power_in"))
      (node (ref "J201") (pin "12") (pinfunction "12_12") (pintype "power_in"))
      (node (ref "J201") (pin "14") (pinfunction "14_14") (pintype "power_in"))
      (node (ref "J201") (pin "16") (pinfunction "16_16") (pintype "power_in"))
      (node (ref "J201") (pin "18") (pinfunction "18_18") (pintype "power_in"))
      (node (ref "J201") (pin "20") (pinfunction "20_20") (pintype "power_in"))
      (node (ref "J201") (pin "22") (pinfunction "22_22") (pintype "power_in"))
      (node (ref "J201") (pin "27") (pinfunction "27_27") (pintype "power_in"))
      (node (ref "J201") (pin "37") (pinfunction "37_37") (pintype "power_in"))
      (node (ref "J201") (pin "47") (pinfunction "47_47") (pintype "power_in"))
      (node (ref "J201") (pin "58") (pinfunction "58_58") (pintype "power_in"))
      (node (ref "J201") (pin "60") (pinfunction "60_60") (pintype "power_in"))
      (node (ref "J201") (pin "62") (pinfunction "62_62") (pintype "power_in"))
      (node (ref "J201") (pin "64") (pinfunction "64_64") (pintype "power_in"))
      (node (ref "J201") (pin "66") (pinfunction "66_66") (pintype "power_in"))
      (node (ref "J201") (pin "68") (pinfunction "68_68") (pintype "power_in"))
      (node (ref "J201") (pin "70") (pinfunction "70_70") (pintype "power_in"))
      (node (ref "J201") (pin "72") (pinfunction "72_72") (pintype "power_in"))
      (node (ref "J201") (pin "8") (pinfunction "8_8") (pintype "power_in"))
      (node (ref "J209") (pin "15") (pinfunction "15_15") (pintype "power_in"))
      (node (ref "J209") (pin "37") (pinfunction "37_37") (pintype "power_in"))
      (node (ref "J209") (pin "59") (pinfunction "59_59") (pintype "power_in"))
      (node (ref "J210") (pin "1") (pinfunction "1_1") (pintype "passive"))
      (node (ref "J210") (pin "11") (pinfunction "11_11") (pintype "passive"))
      (node (ref "J210") (pin "13") (pinfunction "13_13") (pintype "passive"))
      (node (ref "J210") (pin "15") (pinfunction "15_15") (pintype "passive"))
      (node (ref "J210") (pin "17") (pinfunction "17_17") (pintype "passive"))
      (node (ref "J210") (pin "19") (pinfunction "19_19") (pintype "passive"))
      (node (ref "J210") (pin "21") (pinfunction "21_21") (pintype "passive"))
      (node (ref "J210") (pin "23") (pinfunction "23_23") (pintype "passive"))
      (node (ref "J210") (pin "25") (pinfunction "25_25") (pintype "passive"))
      (node (ref "J210") (pin "27") (pinfunction "27_27") (pintype "passive"))
      (node (ref "J210") (pin "29") (pinfunction "29_29") (pintype "passive"))
      (node (ref "J210") (pin "3") (pinfunction "3_3") (pintype "passive"))
      (node (ref "J210") (pin "31") (pinfunction "31_31") (pintype "passive"))
      (node (ref "J210") (pin "33") (pinfunction "33_33") (pintype "passive"))
      (node (ref "J210") (pin "35") (pinfunction "35_35") (pintype "passive"))
      (node (ref "J210") (pin "37") (pinfunction "37_37") (pintype "passive"))
      (node (ref "J210") (pin "39") (pinfunction "39_39") (pintype "passive"))
      (node (ref "J210") (pin "5") (pinfunction "5_5") (pintype "passive"))
      (node (ref "J210") (pin "7") (pinfunction "7_7") (pintype "passive"))
      (node (ref "J210") (pin "9") (pinfunction "9_9") (pintype "passive"))
      (node (ref "L200") (pin "2") (pinfunction "2_2") (pintype "passive"))
      (node (ref "P206") (pin "1") (pinfunction "1_1") (pintype "passive"))
      (node (ref "P206") (pin "10") (pinfunction "10_10") (pintype "passive"))
      (node (ref "P207") (pin "1") (pinfunction "1_1") (pintype "passive"))
      (node (ref "P207") (pin "10") (pinfunction "10_10") (pintype "passive"))
      (node (ref "P208") (pin "10") (pinfunction "10_10") (pintype "passive"))
      (node (ref "P209") (pin "10") (pinfunction "10_10") (pintype "passive"))
      (node (ref "P209") (pin "12") (pinfunction "12_12") (pintype "passive"))
      (node (ref "P209") (pin "4") (pinfunction "4_4") (pintype "passive"))
      (node (ref "P209") (pin "8") (pinfunction "8_8") (pintype "passive"))
      (node (ref "P210") (pin "10") (pinfunction "10_10") (pintype "passive"))
      (node (ref "R200") (pin "2") (pinfunction "2_2") (pintype "passive"))
      (node (ref "U200") (pin "2") (pinfunction "GND_2") (pintype "power_in"))
      (node (ref "U201") (pin "2") (pinfunction "GND_2") (pintype "power_in"))
    )
    (net (code "104") (name "Net-(LED200-K)") (class "Default")
      (node (ref "LED200") (pin "1") (pinfunction "K_1") (pintype "passive"))
      (node (ref "R200") (pin "1") (pinfunction "1_1") (pintype "passive"))
    )
    (net (code "105") (name "VCC_5V") (class "Default")
      (node (ref "C201") (pin "2") (pinfunction "2_2") (pintype "passive"))
      (node (ref "C203") (pin "2") (pinfunction "2_2") (pintype "passive"))
      (node (ref "J200") (pin "112") (pinfunction "112_112") (pintype "passive"))
      (node (ref "J200") (pin "48") (pinfunction "48_48") (pintype "passive"))
      (node (ref "J200") (pin "84") (pinfunction "84_84") (pintype "passive"))
      (node (ref "J200") (pin "98") (pinfunction "98_98") (pintype "passive"))
      (node (ref "J201") (pin "77") (pinfunction "77_77") (pintype "power_in"))
      (node (ref "J201") (pin "82") (pinfunction "82_82") (pintype "power_in"))
      (node (ref "J201") (pin "87") (pinfunction "87_87") (pintype "power_in"))
      (node (ref "J201") (pin "92") (pinfunction "92_92") (pintype "power_in"))
      (node (ref "J201") (pin "96") (pinfunction "96_96") (pintype "power_in"))
      (node (ref "J209") (pin "38") (pinfunction "38_38") (pintype "power_in"))
      (node (ref "J209") (pin "60") (pinfunction "60_60") (pintype "power_in"))
      (node (ref "J210") (pin "16") (pinfunction "16_16") (pintype "passive"))
      (node (ref "J210") (pin "18") (pinfunction "18_18") (pintype "passive"))
      (node (ref "J210") (pin "20") (pinfunction "20_20") (pintype "passive"))
      (node (ref "LED200") (pin "2") (pinfunction "A_2") (pintype "passive"))
      (node (ref "U200") (pin "1") (pinfunction "VIN_1") (pintype "power_in"))
      (node (ref "U200") (pin "3") (pinfunction "EN_3") (pintype "input"))
      (node (ref "U201") (pin "1") (pinfunction "VIN_1") (pintype "power_in"))
      (node (ref "U201") (pin "3") (pinfunction "EN_3") (pintype "input"))
    )
    (net (code "106") (name "unconnected-(J200-Pad1)") (class "Default")
      (node (ref "J200") (pin "1") (pinfunction "1_1") (pintype "passive"))
    )
    (net (code "107") (name "unconnected-(J200-Pad2)") (class "Default")
      (node (ref "J200") (pin "2") (pinfunction "2_2") (pintype "passive"))
    )
    (net (code "108") (name "unconnected-(J200-Pad3)") (class "Default")
      (node (ref "J200") (pin "3") (pinfunction "3_3") (pintype "passive"))
    )
    (net (code "109") (name "unconnected-(J200-Pad4)") (class "Default")
      (node (ref "J200") (pin "4") (pinfunction "4_4") (pintype "passive"))
    )
    (net (code "110") (name "unconnected-(J200-Pad5)") (class "Default")
      (node (ref "J200") (pin "5") (pinfunction "5_5") (pintype "passive"))
    )
    (net (code "111") (name "unconnected-(J200-Pad6)") (class "Default")
      (node (ref "J200") (pin "6") (pinfunction "6_6") (pintype "passive"))
    )
    (net (code "112") (name "unconnected-(J200-Pad8)") (class "Default")
      (node (ref "J200") (pin "8") (pinfunction "8_8") (pintype "passive"))
    )
    (net (code "113") (name "unconnected-(J200-Pad31)") (class "Default")
      (node (ref "J200") (pin "31") (pinfunction "31_31") (pintype "passive"))
    )
    (net (code "114") (name "unconnected-(J200-Pad32)") (class "Default")
      (node (ref "J200") (pin "32") (pinfunction "32_32") (pintype "passive"))
    )
    (net (code "115") (name "unconnected-(J200-Pad33)") (class "Default")
      (node (ref "J200") (pin "33") (pinfunction "33_33") (pintype "passive"))
    )
    (net (code "116") (name "unconnected-(J200-Pad34)") (class "Default")
      (node (ref "J200") (pin "34") (pinfunction "34_34") (pintype "passive"))
    )
    (net (code "117") (name "unconnected-(J200-Pad36)") (class "Default")
      (node (ref "J200") (pin "36") (pinfunction "36_36") (pintype "passive"))
    )
    (net (code "118") (name "unconnected-(J200-Pad37)") (class "Default")
      (node (ref "J200") (pin "37") (pinfunction "37_37") (pintype "passive"))
    )
    (net (code "119") (name "unconnected-(J200-Pad39)") (class "Default")
      (node (ref "J200") (pin "39") (pinfunction "39_39") (pintype "passive"))
    )
    (net (code "120") (name "unconnected-(J200-Pad40)") (class "Default")
      (node (ref "J200") (pin "40") (pinfunction "40_40") (pintype "passive"))
    )
    (net (code "121") (name "unconnected-(J200-Pad41)") (class "Default")
      (node (ref "J200") (pin "41") (pinfunction "41_41") (pintype "passive"))
    )
    (net (code "122") (name "unconnected-(J200-Pad42)") (class "Default")
      (node (ref "J200") (pin "42") (pinfunction "42_42") (pintype "passive"))
    )
    (net (code "123") (name "unconnected-(J200-Pad43)") (class "Default")
      (node (ref "J200") (pin "43") (pinfunction "43_43") (pintype "passive"))
    )
    (net (code "124") (name "unconnected-(J200-Pad44)") (class "Default")
      (node (ref "J200") (pin "44") (pinfunction "44_44") (pintype "passive"))
    )
    (net (code "125") (name "unconnected-(J200-Pad45)") (class "Default")
      (node (ref "J200") (pin "45") (pinfunction "45_45") (pintype "passive"))
    )
    (net (code "126") (name "unconnected-(J200-Pad66)") (class "Default")
      (node (ref "J200") (pin "66") (pinfunction "66_66") (pintype "passive"))
    )
    (net (code "127") (name "unconnected-(J200-Pad76)") (class "Default")
      (node (ref "J200") (pin "76") (pinfunction "76_76") (pintype "passive"))
    )
    (net (code "128") (name "unconnected-(J200-Pad78)") (class "Default")
      (node (ref "J200") (pin "78") (pinfunction "78_78") (pintype "passive"))
    )
    (net (code "129") (name "unconnected-(J200-Pad80)") (class "Default")
      (node (ref "J200") (pin "80") (pinfunction "80_80") (pintype "passive"))
    )
    (net (code "130") (name "unconnected-(J200-Pad82)") (class "Default")
      (node (ref "J200") (pin "82") (pinfunction "82_82") (pintype "passive"))
    )
    (net (code "131") (name "unconnected-(J200-Pad86)") (class "Default")
      (node (ref "J200") (pin "86") (pinfunction "86_86") (pintype "passive"))
    )
    (net (code "132") (name "unconnected-(J200-Pad92)") (class "Default")
      (node (ref "J200") (pin "92") (pinfunction "92_92") (pintype "passive"))
    )
    (net (code "133") (name "unconnected-(J200-Pad93)") (class "Default")
      (node (ref "J200") (pin "93") (pinfunction "93_93") (pintype "passive"))
    )
    (net (code "134") (name "unconnected-(J200-Pad94)") (class "Default")
      (node (ref "J200") (pin "94") (pinfunction "94_94") (pintype "passive"))
    )
    (net (code "135") (name "unconnected-(J200-Pad95)") (class "Default")
      (node (ref "J200") (pin "95") (pinfunction "95_95") (pintype "passive"))
    )
    (net (code "136") (name "unconnected-(J200-Pad96)") (class "Default")
      (node (ref "J200") (pin "96") (pinfunction "96_96") (pintype "passive"))
    )
    (net (code "137") (name "unconnected-(J200-Pad99)") (class "Default")
      (node (ref "J200") (pin "99") (pinfunction "99_99") (pintype "passive"))
    )
    (net (code "138") (name "unconnected-(J200-Pad101)") (class "Default")
      (node (ref "J200") (pin "101") (pinfunction "101_101") (pintype "passive"))
    )
    (net (code "139") (name "unconnected-(J200-Pad103)") (class "Default")
      (node (ref "J200") (pin "103") (pinfunction "103_103") (pintype "passive"))
    )
    (net (code "140") (name "unconnected-(J200-Pad105)") (class "Default")
      (node (ref "J200") (pin "105") (pinfunction "105_105") (pintype "passive"))
    )
    (net (code "141") (name "unconnected-(J200-Pad107)") (class "Default")
      (node (ref "J200") (pin "107") (pinfunction "107_107") (pintype "passive"))
    )
    (net (code "142") (name "unconnected-(J200-Pad108)") (class "Default")
      (node (ref "J200") (pin "108") (pinfunction "108_108") (pintype "passive"))
    )
    (net (code "143") (name "unconnected-(J200-Pad109)") (class "Default")
      (node (ref "J200") (pin "109") (pinfunction "109_109") (pintype "passive"))
    )
    (net (code "144") (name "unconnected-(J200-Pad110)") (class "Default")
      (node (ref "J200") (pin "110") (pinfunction "110_110") (pintype "passive"))
    )
    (net (code "145") (name "unconnected-(J200-Pad113)") (class "Default")
      (node (ref "J200") (pin "113") (pinfunction "113_113") (pintype "passive"))
    )
    (net (code "146") (name "unconnected-(J200-Pad114)") (class "Default")
      (node (ref "J200") (pin "114") (pinfunction "114_114") (pintype "passive"))
    )
    (net (code "147") (name "unconnected-(J200-Pad115)") (class "Default")
      (node (ref "J200") (pin "115") (pinfunction "115_115") (pintype "passive"))
    )
    (net (code "148") (name "unconnected-(J200-Pad116)") (class "Default")
      (node (ref "J200") (pin "116") (pinfunction "116_116") (pintype "passive"))
    )
    (net (code "149") (name "unconnected-(J200-Pad117)") (class "Default")
      (node (ref "J200") (pin "117") (pinfunction "117_117") (pintype "passive"))
    )
    (net (code "150") (name "unconnected-(J200-Pad118)") (class "Default")
      (node (ref "J200") (pin "118") (pinfunction "118_118") (pintype "passive"))
    )
    (net (code "151") (name "unconnected-(J200-Pad119)") (class "Default")
      (node (ref "J200") (pin "119") (pinfunction "119_119") (pintype "passive"))
    )
    (net (code "152") (name "unconnected-(J200-SHIELD-PadP1)") (class "Default")
      (node (ref "J200") (pin "P1") (pinfunction "SHIELD_P1") (pintype "passive"))
    )
    (net (code "153") (name "unconnected-(J200-SHIELD-PadP2)") (class "Default")
      (node (ref "J200") (pin "P2") (pinfunction "SHIELD_P2") (pintype "passive"))
    )
    (net (code "154") (name "unconnected-(J201-Pad1)") (class "Default")
      (node (ref "J201") (pin "1") (pinfunction "1_1") (pintype "power_in"))
    )
    (net (code "155") (name "unconnected-(J201-Pad2)") (class "Default")
      (node (ref "J201") (pin "2") (pinfunction "2_2") (pintype "power_in"))
    )
    (net (code "156") (name "unconnected-(J201-Pad3)") (class "Default")
      (node (ref "J201") (pin "3") (pinfunction "3_3") (pintype "power_in"))
    )
    (net (code "157") (name "unconnected-(J201-Pad4)") (class "Default")
      (node (ref "J201") (pin "4") (pinfunction "4_4") (pintype "power_in"))
    )
    (net (code "158") (name "unconnected-(J201-Pad5)") (class "Default")
      (node (ref "J201") (pin "5") (pinfunction "5_5") (pintype "power_in"))
    )
    (net (code "159") (name "unconnected-(J201-Pad6)") (class "Default")
      (node (ref "J201") (pin "6") (pinfunction "6_6") (pintype "power_in"))
    )
    (net (code "160") (name "unconnected-(J201-Pad31)") (class "Default")
      (node (ref "J201") (pin "31") (pinfunction "31_31") (pintype "power_in"))
    )
    (net (code "161") (name "unconnected-(J201-Pad32)") (class "Default")
      (node (ref "J201") (pin "32") (pinfunction "32_32") (pintype "power_in"))
    )
    (net (code "162") (name "unconnected-(J201-Pad41)") (class "Default")
      (node (ref "J201") (pin "41") (pinfunction "41_41") (pintype "power_in"))
    )
    (net (code "163") (name "unconnected-(J201-Pad42)") (class "Default")
      (node (ref "J201") (pin "42") (pinfunction "42_42") (pintype "power_in"))
    )
    (net (code "164") (name "unconnected-(J201-Pad43)") (class "Default")
      (node (ref "J201") (pin "43") (pinfunction "43_43") (pintype "power_in"))
    )
    (net (code "165") (name "unconnected-(J201-Pad44)") (class "Default")
      (node (ref "J201") (pin "44") (pinfunction "44_44") (pintype "power_in"))
    )
    (net (code "166") (name "unconnected-(J201-Pad46)") (class "Default")
      (node (ref "J201") (pin "46") (pinfunction "46_46") (pintype "power_in"))
    )
    (net (code "167") (name "unconnected-(J201-Pad51)") (class "Default")
      (node (ref "J201") (pin "51") (pinfunction "51_51") (pintype "power_in"))
    )
    (net (code "168") (name "unconnected-(J201-Pad52)") (class "Default")
      (node (ref "J201") (pin "52") (pinfunction "52_52") (pintype "power_in"))
    )
    (net (code "169") (name "unconnected-(J201-Pad53)") (class "Default")
      (node (ref "J201") (pin "53") (pinfunction "53_53") (pintype "power_in"))
    )
    (net (code "170") (name "unconnected-(J201-Pad54)") (class "Default")
      (node (ref "J201") (pin "54") (pinfunction "54_54") (pintype "power_in"))
    )
    (net (code "171") (name "unconnected-(J201-Pad55)") (class "Default")
      (node (ref "J201") (pin "55") (pinfunction "55_55") (pintype "power_in"))
    )
    (net (code "172") (name "unconnected-(J201-Pad56)") (class "Default")
      (node (ref "J201") (pin "56") (pinfunction "56_56") (pintype "power_in"))
    )
    (net (code "173") (name "unconnected-(J201-Pad81)") (class "Default")
      (node (ref "J201") (pin "81") (pinfunction "81_81") (pintype "power_in"))
    )
    (net (code "174") (name "unconnected-(J201-Pad86)") (class "Default")
      (node (ref "J201") (pin "86") (pinfunction "86_86") (pintype "power_in"))
    )
    (net (code "175") (name "unconnected-(J201-Pad93)") (class "Default")
      (node (ref "J201") (pin "93") (pinfunction "93_93") (pintype "power_in"))
    )
    (net (code "176") (name "unconnected-(J201-Pad94)") (class "Default")
      (node (ref "J201") (pin "94") (pinfunction "94_94") (pintype "power_in"))
    )
    (net (code "177") (name "unconnected-(J209-Pad1)") (class "Default")
      (node (ref "J209") (pin "1") (pinfunction "1_1") (pintype "power_in"))
    )
    (net (code "178") (name "unconnected-(J209-Pad2)") (class "Default")
      (node (ref "J209") (pin "2") (pinfunction "2_2") (pintype "power_in"))
    )
    (net (code "179") (name "unconnected-(J209-Pad3)") (class "Default")
      (node (ref "J209") (pin "3") (pinfunction "3_3") (pintype "power_in"))
    )
    (net (code "180") (name "unconnected-(J209-Pad4)") (class "Default")
      (node (ref "J209") (pin "4") (pinfunction "4_4") (pintype "power_in"))
    )
    (net (code "181") (name "unconnected-(J209-Pad5)") (class "Default")
      (node (ref "J209") (pin "5") (pinfunction "5_5") (pintype "power_in"))
    )
    (net (code "182") (name "unconnected-(J209-Pad6)") (class "Default")
      (node (ref "J209") (pin "6") (pinfunction "6_6") (pintype "power_in"))
    )
    (net (code "183") (name "unconnected-(J209-Pad7)") (class "Default")
      (node (ref "J209") (pin "7") (pinfunction "7_7") (pintype "power_in"))
    )
    (net (code "184") (name "unconnected-(J209-Pad8)") (class "Default")
      (node (ref "J209") (pin "8") (pinfunction "8_8") (pintype "power_in"))
    )
    (net (code "185") (name "unconnected-(J209-Pad9)") (class "Default")
      (node (ref "J209") (pin "9") (pinfunction "9_9") (pintype "power_in"))
    )
    (net (code "186") (name "unconnected-(J209-Pad10)") (class "Default")
      (node (ref "J209") (pin "10") (pinfunction "10_10") (pintype "power_in"))
    )
    (net (code "187") (name "unconnected-(J209-Pad11)") (class "Default")
      (node (ref "J209") (pin "11") (pinfunction "11_11") (pintype "power_in"))
    )
    (net (code "188") (name "unconnected-(J209-Pad12)") (class "Default")
      (node (ref "J209") (pin "12") (pinfunction "12_12") (pintype "power_in"))
    )
    (net (code "189") (name "unconnected-(J209-Pad13)") (class "Default")
      (node (ref "J209") (pin "13") (pinfunction "13_13") (pintype "power_in"))
    )
    (net (code "190") (name "unconnected-(J209-Pad14)") (class "Default")
      (node (ref "J209") (pin "14") (pinfunction "14_14") (pintype "power_in"))
    )
    (net (code "191") (name "unconnected-(J209-Pad16)") (class "Default")
      (node (ref "J209") (pin "16") (pinfunction "16_16") (pintype "power_in"))
    )
    (net (code "192") (name "unconnected-(J209-Pad17)") (class "Default")
      (node (ref "J209") (pin "17") (pinfunction "17_17") (pintype "power_in"))
    )
    (net (code "193") (name "unconnected-(J209-Pad18)") (class "Default")
      (node (ref "J209") (pin "18") (pinfunction "18_18") (pintype "power_in"))
    )
    (net (code "194") (name "unconnected-(J209-Pad19)") (class "Default")
      (node (ref "J209") (pin "19") (pinfunction "19_19") (pintype "power_in"))
    )
    (net (code "195") (name "unconnected-(J209-Pad20)") (class "Default")
      (node (ref "J209") (pin "20") (pinfunction "20_20") (pintype "power_in"))
    )
    (net (code "196") (name "unconnected-(J209-Pad21)") (class "Default")
      (node (ref "J209") (pin "21") (pinfunction "21_21") (pintype "power_in"))
    )
    (net (code "197") (name "unconnected-(J209-Pad22)") (class "Default")
      (node (ref "J209") (pin "22") (pinfunction "22_22") (pintype "power_in"))
    )
    (net (code "198") (name "unconnected-(J209-Pad23)") (class "Default")
      (node (ref "J209") (pin "23") (pinfunction "23_23") (pintype "power_in"))
    )
    (net (code "199") (name "unconnected-(J209-Pad24)") (class "Default")
      (node (ref "J209") (pin "24") (pinfunction "24_24") (pintype "power_in"))
    )
    (net (code "200") (name "unconnected-(J209-Pad25)") (class "Default")
      (node (ref "J209") (pin "25") (pinfunction "25_25") (pintype "power_in"))
    )
    (net (code "201") (name "unconnected-(J209-Pad26)") (class "Default")
      (node (ref "J209") (pin "26") (pinfunction "26_26") (pintype "power_in"))
    )
    (net (code "202") (name "unconnected-(J209-Pad27)") (class "Default")
      (node (ref "J209") (pin "27") (pinfunction "27_27") (pintype "power_in"))
    )
    (net (code "203") (name "unconnected-(J209-Pad28)") (class "Default")
      (node (ref "J209") (pin "28") (pinfunction "28_28") (pintype "power_in"))
    )
    (net (code "204") (name "unconnected-(J209-Pad29)") (class "Default")
      (node (ref "J209") (pin "29") (pinfunction "29_29") (pintype "power_in"))
    )
    (net (code "205") (name "unconnected-(J209-Pad30)") (class "Default")
      (node (ref "J209") (pin "30") (pinfunction "30_30") (pintype "power_in"))
    )
    (net (code "206") (name "unconnected-(J209-Pad31)") (class "Default")
      (node (ref "J209") (pin "31") (pinfunction "31_31") (pintype "power_in"))
    )
    (net (code "207") (name "unconnected-(J209-Pad32)") (class "Default")
      (node (ref "J209") (pin "32") (pinfunction "32_32") (pintype "power_in"))
    )
    (net (code "208") (name "unconnected-(J209-Pad33)") (class "Default")
      (node (ref "J209") (pin "33") (pinfunction "33_33") (pintype "power_in"))
    )
    (net (code "209") (name "unconnected-(J209-Pad34)") (class "Default")
      (node (ref "J209") (pin "34") (pinfunction "34_34") (pintype "power_in"))
    )
    (net (code "210") (name "unconnected-(J209-Pad35)") (class "Default")
      (node (ref "J209") (pin "35") (pinfunction "35_35") (pintype "power_in"))
    )
    (net (code "211") (name "unconnected-(J209-Pad36)") (class "Default")
      (node (ref "J209") (pin "36") (pinfunction "36_36") (pintype "power_in"))
    )
    (net (code "212") (name "unconnected-(J209-Pad39)") (class "Default")
      (node (ref "J209") (pin "39") (pinfunction "39_39") (pintype "power_in"))
    )
    (net (code "213") (name "unconnected-(J209-Pad40)") (class "Default")
      (node (ref "J209") (pin "40") (pinfunction "40_40") (pintype "power_in"))
    )
    (net (code "214") (name "unconnected-(J209-Pad41)") (class "Default")
      (node (ref "J209") (pin "41") (pinfunction "41_41") (pintype "power_in"))
    )
    (net (code "215") (name "unconnected-(J209-Pad42)") (class "Default")
      (node (ref "J209") (pin "42") (pinfunction "42_42") (pintype "power_in"))
    )
    (net (code "216") (name "unconnected-(J209-Pad43)") (class "Default")
      (node (ref "J209") (pin "43") (pinfunction "43_43") (pintype "power_in"))
    )
    (net (code "217") (name "unconnected-(J209-Pad44)") (class "Default")
      (node (ref "J209") (pin "44") (pinfunction "44_44") (pintype "power_in"))
    )
    (net (code "218") (name "unconnected-(J209-Pad45)") (class "Default")
      (node (ref "J209") (pin "45") (pinfunction "45_45") (pintype "power_in"))
    )
    (net (code "219") (name "unconnected-(J209-Pad46)") (class "Default")
      (node (ref "J209") (pin "46") (pinfunction "46_46") (pintype "power_in"))
    )
    (net (code "220") (name "unconnected-(J209-Pad47)") (class "Default")
      (node (ref "J209") (pin "47") (pinfunction "47_47") (pintype "power_in"))
    )
    (net (code "221") (name "unconnected-(J209-Pad48)") (class "Default")
      (node (ref "J209") (pin "48") (pinfunction "48_48") (pintype "power_in"))
    )
    (net (code "222") (name "unconnected-(J209-Pad49)") (class "Default")
      (node (ref "J209") (pin "49") (pinfunction "49_49") (pintype "power_in"))
    )
    (net (code "223") (name "unconnected-(J209-Pad50)") (class "Default")
      (node (ref "J209") (pin "50") (pinfunction "50_50") (pintype "power_in"))
    )
    (net (code "224") (name "unconnected-(J209-Pad51)") (class "Default")
      (node (ref "J209") (pin "51") (pinfunction "51_51") (pintype "power_in"))
    )
    (net (code "225") (name "unconnected-(J209-Pad52)") (class "Default")
      (node (ref "J209") (pin "52") (pinfunction "52_52") (pintype "power_in"))
    )
    (net (code "226") (name "unconnected-(J209-Pad53)") (class "Default")
      (node (ref "J209") (pin "53") (pinfunction "53_53") (pintype "power_in"))
    )
    (net (code "227") (name "unconnected-(J209-Pad54)") (class "Default")
      (node (ref "J209") (pin "54") (pinfunction "54_54") (pintype "power_in"))
    )
    (net (code "228") (name "unconnected-(J209-Pad55)") (class "Default")
      (node (ref "J209") (pin "55") (pinfunction "55_55") (pintype "power_in"))
    )
    (net (code "229") (name "unconnected-(J209-Pad56)") (class "Default")
      (node (ref "J209") (pin "56") (pinfunction "56_56") (pintype "power_in"))
    )
    (net (code "230") (name "unconnected-(J209-Pad57)") (class "Default")
      (node (ref "J209") (pin "57") (pinfunction "57_57") (pintype "power_in"))
    )
    (net (code "231") (name "unconnected-(J209-Pad58)") (class "Default")
      (node (ref "J209") (pin "58") (pinfunction "58_58") (pintype "power_in"))
    )
    (net (code "232") (name "unconnected-(J210-Pad10)") (class "Default")
      (node (ref "J210") (pin "10") (pinfunction "10_10") (pintype "passive"))
    )
    (net (code "233") (name "unconnected-(J210-Pad12)") (class "Default")
      (node (ref "J210") (pin "12") (pinfunction "12_12") (pintype "passive"))
    )
    (net (code "234") (name "unconnected-(J210-Pad14)") (class "Default")
      (node (ref "J210") (pin "14") (pinfunction "14_14") (pintype "passive"))
    )
    (net (code "235") (name "unconnected-(J210-Pad22)") (class "Default")
      (node (ref "J210") (pin "22") (pinfunction "22_22") (pintype "passive"))
    )
    (net (code "236") (name "unconnected-(J210-Pad24)") (class "Default")
      (node (ref "J210") (pin "24") (pinfunction "24_24") (pintype "passive"))
    )
    (net (code "237") (name "unconnected-(J210-Pad26)") (class "Default")
      (node (ref "J210") (pin "26") (pinfunction "26_26") (pintype "passive"))
    )
    (net (code "238") (name "unconnected-(J210-Pad28)") (class "Default")
      (node (ref "J210") (pin "28") (pinfunction "28_28") (pintype "passive"))
    )
    (net (code "239") (name "unconnected-(P208-Pad1)") (class "Default")
      (node (ref "P208") (pin "1") (pinfunction "1_1") (pintype "passive"))
    )
    (net (code "240") (name "unconnected-(P208-Pad2)") (class "Default")
      (node (ref "P208") (pin "2") (pinfunction "2_2") (pintype "passive"))
    )
    (net (code "241") (name "unconnected-(P209-Pad5)") (class "Default")
      (node (ref "P209") (pin "5") (pinfunction "5_5") (pintype "passive"))
    )
    (net (code "242") (name "unconnected-(P209-Pad6)") (class "Default")
      (node (ref "P209") (pin "6") (pinfunction "6_6") (pintype "passive"))
    )
    (net (code "243") (name "unconnected-(P210-Pad1)") (class "Default")
      (node (ref "P210") (pin "1") (pinfunction "1_1") (pintype "passive"))
    )
    (net (code "244") (name "unconnected-(P210-Pad2)") (class "Default")
      (node (ref "P210") (pin "2") (pinfunction "2_2") (pintype "passive"))
    )
    (net (code "245") (name "unconnected-(U200-NC-Pad4)") (class "Default")
      (node (ref "U200") (pin "4") (pinfunction "NC_4") (pintype "passive"))
    )
    (net (code "246") (name "unconnected-(U201-NC-Pad4)") (class "Default")
      (node (ref "U201") (pin "4") (pinfunction "NC_4") (pintype "passive"))
    )
  )
)
